# Ring_5_D.net
KiCad netlist of a schematic drawn in Altium Designer
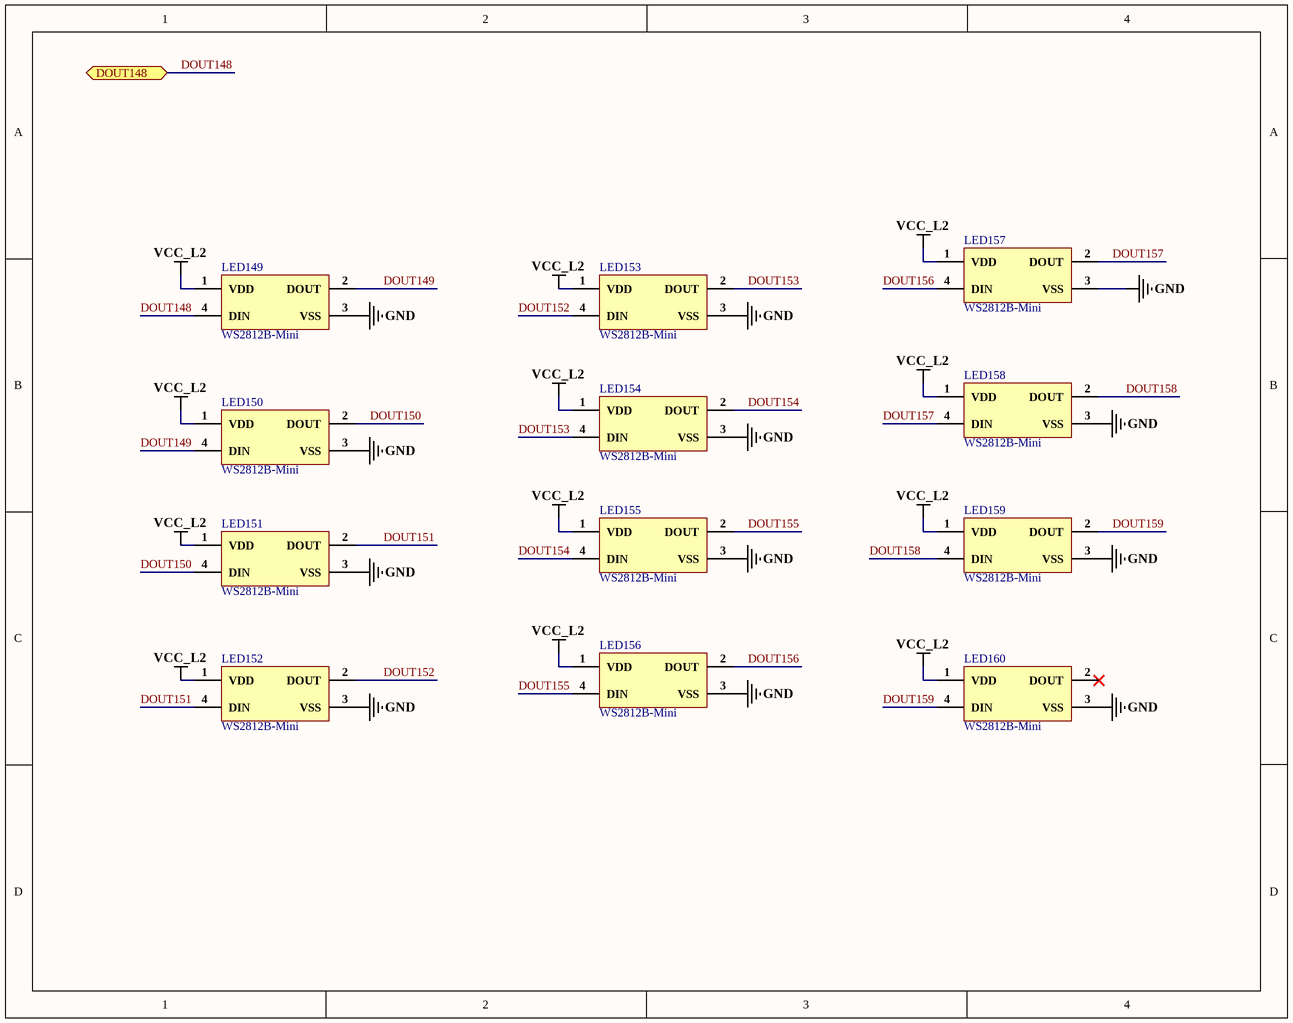
[diagram p0: Ring 5_D.SchDoc]

(export (version "E")
  (design (tool "Eeschema 10.0.6"))
  (components
    (comp (ref "LED149")
      (value "WS2812B-Mini")
      (footprint "WS2812B-Mini")
      (description "SMD,3.5x3.5mm Light Emitting Diodes (LED) RoHS")
      (fields (field (name "MANUFACTURER") "Worldsemi"))
      (libsource (lib "TT_IntLib") (part "WS2812B-Mini"))
    )
    (comp (ref "LED150")
      (value "WS2812B-Mini")
      (footprint "WS2812B-Mini")
      (description "SMD,3.5x3.5mm Light Emitting Diodes (LED) RoHS")
      (fields (field (name "MANUFACTURER") "Worldsemi"))
      (libsource (lib "TT_IntLib") (part "WS2812B-Mini"))
    )
    (comp (ref "LED151")
      (value "WS2812B-Mini")
      (footprint "WS2812B-Mini")
      (description "SMD,3.5x3.5mm Light Emitting Diodes (LED) RoHS")
      (fields (field (name "MANUFACTURER") "Worldsemi"))
      (libsource (lib "TT_IntLib") (part "WS2812B-Mini"))
    )
    (comp (ref "LED152")
      (value "WS2812B-Mini")
      (footprint "WS2812B-Mini")
      (description "SMD,3.5x3.5mm Light Emitting Diodes (LED) RoHS")
      (fields (field (name "MANUFACTURER") "Worldsemi"))
      (libsource (lib "TT_IntLib") (part "WS2812B-Mini"))
    )
    (comp (ref "LED153")
      (value "WS2812B-Mini")
      (footprint "WS2812B-Mini")
      (description "SMD,3.5x3.5mm Light Emitting Diodes (LED) RoHS")
      (fields (field (name "MANUFACTURER") "Worldsemi"))
      (libsource (lib "TT_IntLib") (part "WS2812B-Mini"))
    )
    (comp (ref "LED154")
      (value "WS2812B-Mini")
      (footprint "WS2812B-Mini")
      (description "SMD,3.5x3.5mm Light Emitting Diodes (LED) RoHS")
      (fields (field (name "MANUFACTURER") "Worldsemi"))
      (libsource (lib "TT_IntLib") (part "WS2812B-Mini"))
    )
    (comp (ref "LED155")
      (value "WS2812B-Mini")
      (footprint "WS2812B-Mini")
      (description "SMD,3.5x3.5mm Light Emitting Diodes (LED) RoHS")
      (fields (field (name "MANUFACTURER") "Worldsemi"))
      (libsource (lib "TT_IntLib") (part "WS2812B-Mini"))
    )
    (comp (ref "LED156")
      (value "WS2812B-Mini")
      (footprint "WS2812B-Mini")
      (description "SMD,3.5x3.5mm Light Emitting Diodes (LED) RoHS")
      (fields (field (name "MANUFACTURER") "Worldsemi"))
      (libsource (lib "TT_IntLib") (part "WS2812B-Mini"))
    )
    (comp (ref "LED157")
      (value "WS2812B-Mini")
      (footprint "WS2812B-Mini")
      (description "SMD,3.5x3.5mm Light Emitting Diodes (LED) RoHS")
      (fields (field (name "MANUFACTURER") "Worldsemi"))
      (libsource (lib "TT_IntLib") (part "WS2812B-Mini"))
    )
    (comp (ref "LED158")
      (value "WS2812B-Mini")
      (footprint "WS2812B-Mini")
      (description "SMD,3.5x3.5mm Light Emitting Diodes (LED) RoHS")
      (fields (field (name "MANUFACTURER") "Worldsemi"))
      (libsource (lib "TT_IntLib") (part "WS2812B-Mini"))
    )
    (comp (ref "LED159")
      (value "WS2812B-Mini")
      (footprint "WS2812B-Mini")
      (description "SMD,3.5x3.5mm Light Emitting Diodes (LED) RoHS")
      (fields (field (name "MANUFACTURER") "Worldsemi"))
      (libsource (lib "TT_IntLib") (part "WS2812B-Mini"))
    )
    (comp (ref "LED160")
      (value "WS2812B-Mini")
      (footprint "WS2812B-Mini")
      (description "SMD,3.5x3.5mm Light Emitting Diodes (LED) RoHS")
      (fields (field (name "MANUFACTURER") "Worldsemi"))
      (libsource (lib "TT_IntLib") (part "WS2812B-Mini"))
    )
  )
  (nets
    (net (code "1") (name "/DOUT148") (class "Default")
      (node (ref "LED149") (pin "4") (pinfunction "DIN_4") (pintype "passive"))
    )
    (net (code "2") (name "/DOUT149") (class "Default")
      (node (ref "LED149") (pin "2") (pinfunction "DOUT_2") (pintype "passive"))
      (node (ref "LED150") (pin "4") (pinfunction "DIN_4") (pintype "passive"))
    )
    (net (code "3") (name "/DOUT150") (class "Default")
      (node (ref "LED150") (pin "2") (pinfunction "DOUT_2") (pintype "passive"))
      (node (ref "LED151") (pin "4") (pinfunction "DIN_4") (pintype "passive"))
    )
    (net (code "4") (name "/DOUT151") (class "Default")
      (node (ref "LED151") (pin "2") (pinfunction "DOUT_2") (pintype "passive"))
      (node (ref "LED152") (pin "4") (pinfunction "DIN_4") (pintype "passive"))
    )
    (net (code "5") (name "/DOUT152") (class "Default")
      (node (ref "LED152") (pin "2") (pinfunction "DOUT_2") (pintype "passive"))
      (node (ref "LED153") (pin "4") (pinfunction "DIN_4") (pintype "passive"))
    )
    (net (code "6") (name "/DOUT153") (class "Default")
      (node (ref "LED153") (pin "2") (pinfunction "DOUT_2") (pintype "passive"))
      (node (ref "LED154") (pin "4") (pinfunction "DIN_4") (pintype "passive"))
    )
    (net (code "7") (name "/DOUT154") (class "Default")
      (node (ref "LED154") (pin "2") (pinfunction "DOUT_2") (pintype "passive"))
      (node (ref "LED155") (pin "4") (pinfunction "DIN_4") (pintype "passive"))
    )
    (net (code "8") (name "/DOUT155") (class "Default")
      (node (ref "LED155") (pin "2") (pinfunction "DOUT_2") (pintype "passive"))
      (node (ref "LED156") (pin "4") (pinfunction "DIN_4") (pintype "passive"))
    )
    (net (code "9") (name "/DOUT156") (class "Default")
      (node (ref "LED156") (pin "2") (pinfunction "DOUT_2") (pintype "passive"))
      (node (ref "LED157") (pin "4") (pinfunction "DIN_4") (pintype "passive"))
    )
    (net (code "10") (name "/DOUT157") (class "Default")
      (node (ref "LED157") (pin "2") (pinfunction "DOUT_2") (pintype "passive"))
      (node (ref "LED158") (pin "4") (pinfunction "DIN_4") (pintype "passive"))
    )
    (net (code "11") (name "/DOUT158") (class "Default")
      (node (ref "LED158") (pin "2") (pinfunction "DOUT_2") (pintype "passive"))
      (node (ref "LED159") (pin "4") (pinfunction "DIN_4") (pintype "passive"))
    )
    (net (code "12") (name "/DOUT159") (class "Default")
      (node (ref "LED159") (pin "2") (pinfunction "DOUT_2") (pintype "passive"))
      (node (ref "LED160") (pin "4") (pinfunction "DIN_4") (pintype "passive"))
    )
    (net (code "13") (name "GND") (class "Default")
      (node (ref "LED149") (pin "3") (pinfunction "VSS_3") (pintype "passive"))
      (node (ref "LED150") (pin "3") (pinfunction "VSS_3") (pintype "passive"))
      (node (ref "LED151") (pin "3") (pinfunction "VSS_3") (pintype "passive"))
      (node (ref "LED152") (pin "3") (pinfunction "VSS_3") (pintype "passive"))
      (node (ref "LED153") (pin "3") (pinfunction "VSS_3") (pintype "passive"))
      (node (ref "LED154") (pin "3") (pinfunction "VSS_3") (pintype "passive"))
      (node (ref "LED155") (pin "3") (pinfunction "VSS_3") (pintype "passive"))
      (node (ref "LED156") (pin "3") (pinfunction "VSS_3") (pintype "passive"))
      (node (ref "LED157") (pin "3") (pinfunction "VSS_3") (pintype "passive"))
      (node (ref "LED158") (pin "3") (pinfunction "VSS_3") (pintype "passive"))
      (node (ref "LED159") (pin "3") (pinfunction "VSS_3") (pintype "passive"))
      (node (ref "LED160") (pin "3") (pinfunction "VSS_3") (pintype "passive"))
    )
    (net (code "14") (name "VCC_L2") (class "Default")
      (node (ref "LED149") (pin "1") (pinfunction "VDD_1") (pintype "passive"))
      (node (ref "LED150") (pin "1") (pinfunction "VDD_1") (pintype "passive"))
      (node (ref "LED151") (pin "1") (pinfunction "VDD_1") (pintype "passive"))
      (node (ref "LED152") (pin "1") (pinfunction "VDD_1") (pintype "passive"))
      (node (ref "LED153") (pin "1") (pinfunction "VDD_1") (pintype "passive"))
      (node (ref "LED154") (pin "1") (pinfunction "VDD_1") (pintype "passive"))
      (node (ref "LED155") (pin "1") (pinfunction "VDD_1") (pintype "passive"))
      (node (ref "LED156") (pin "1") (pinfunction "VDD_1") (pintype "passive"))
      (node (ref "LED157") (pin "1") (pinfunction "VDD_1") (pintype "passive"))
      (node (ref "LED158") (pin "1") (pinfunction "VDD_1") (pintype "passive"))
      (node (ref "LED159") (pin "1") (pinfunction "VDD_1") (pintype "passive"))
      (node (ref "LED160") (pin "1") (pinfunction "VDD_1") (pintype "passive"))
    )
    (net (code "15") (name "unconnected-(LED160-DOUT-Pad2)") (class "Default")
      (node (ref "LED160") (pin "2") (pinfunction "DOUT_2") (pintype "passive+no_connect"))
    )
  )
)
